# SENSORS.net
KiCad netlist of a schematic drawn in Altium Designer
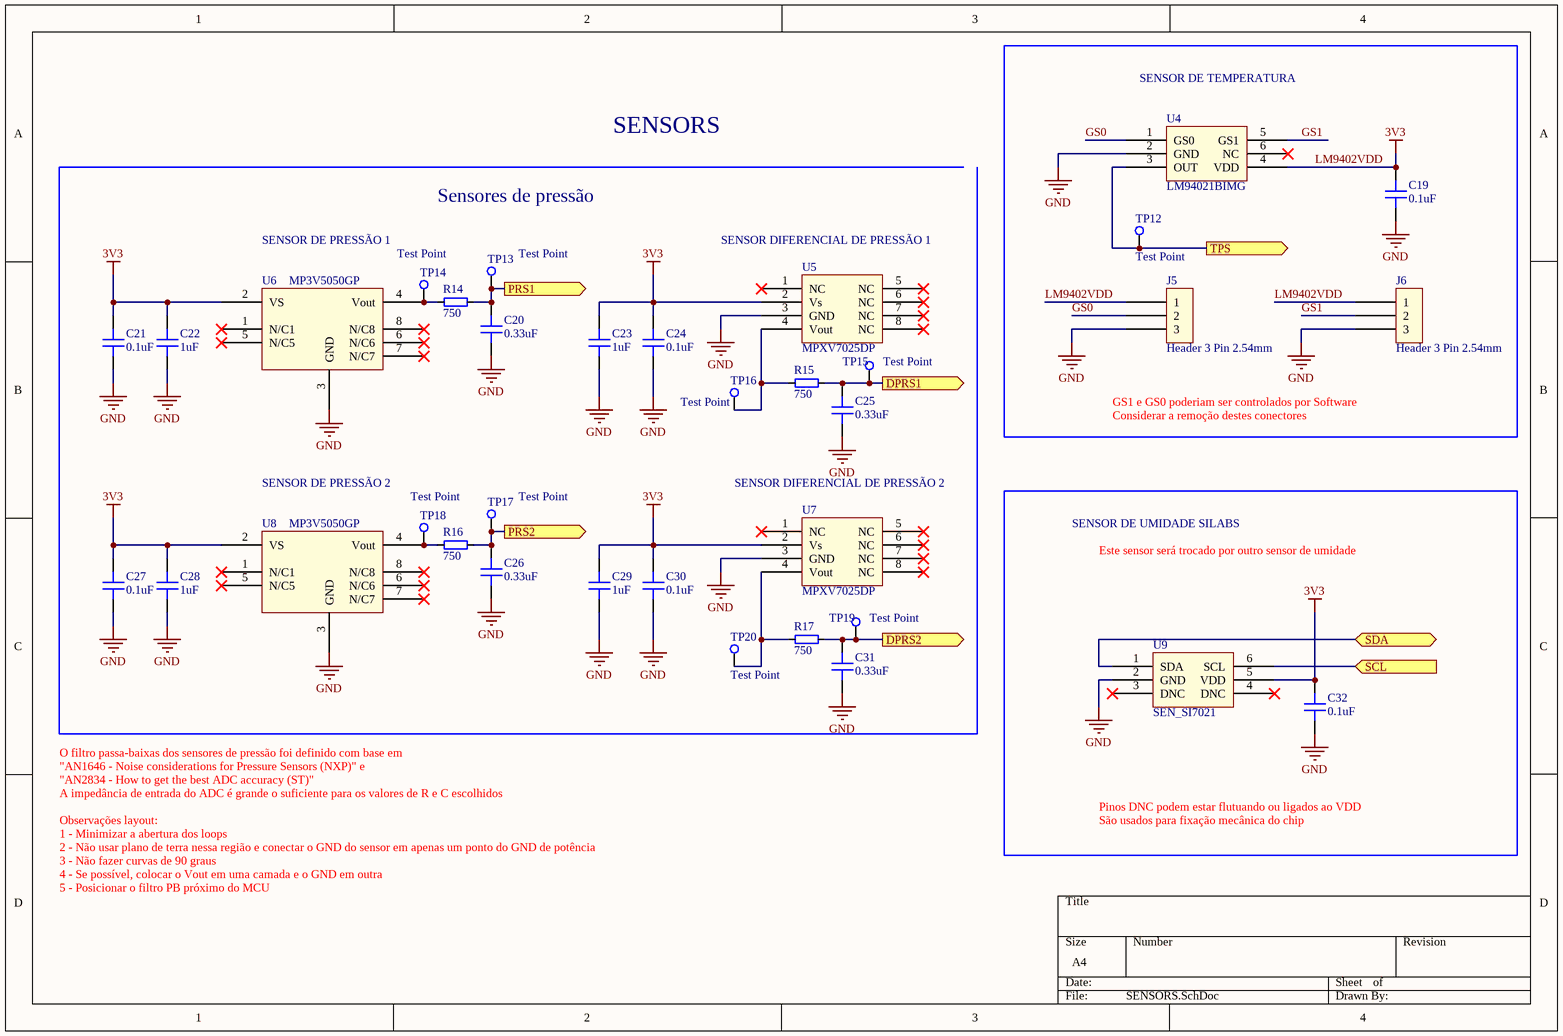
[diagram p0: SENSORS.SchDoc]

(export (version "E")
  (design (tool "Eeschema 10.0.6"))
  (components
    (comp (ref "C19")
      (value "0.1uF")
      (footprint "C_0805")
      (description "SMD/SMT 50V 0.1uF X7R 0805 10% Ceramic")
      (fields (field (name "VOLTAGE") "50V") (field (name "MANUFACTURER") "KEMET"))
      (libsource (lib "RespiradorLib") (part "C_0805_C0805C104K5RAC7411"))
    )
    (comp (ref "C20")
      (value "0.33uF")
      (footprint "C_0805")
      (description "SMD/SMT 50V 0.33uF X7R 0805 10%")
      (fields (field (name "VOLTAGE") "50V") (field (name "MANUFACTURER") "KEMET"))
      (libsource (lib "RespiradorLib") (part "C_0805_C0805C334K5RECTU"))
    )
    (comp (ref "C21")
      (value "0.1uF")
      (footprint "C_0805")
      (description "SMD/SMT 50V 0.1uF X7R 0805 10% Ceramic")
      (fields (field (name "VOLTAGE") "50V") (field (name "MANUFACTURER") "KEMET"))
      (libsource (lib "RespiradorLib") (part "C_0805_C0805C104K5RAC7411"))
    )
    (comp (ref "C22")
      (value "1uF")
      (footprint "C_0805")
      (description "SMD/SMT 0805 50V 1uF 10% AEC-Q200 Ceramic")
      (fields (field (name "VOLTAGE") "50V") (field (name "MANUFACTURER") "Taiyo Yuden"))
      (libsource (lib "RespiradorLib") (part "C_0805_UMF212B7105KGHT"))
    )
    (comp (ref "C23")
      (value "1uF")
      (footprint "C_0805")
      (description "SMD/SMT 0805 50V 1uF 10% AEC-Q200 Ceramic")
      (fields (field (name "VOLTAGE") "50V") (field (name "MANUFACTURER") "Taiyo Yuden"))
      (libsource (lib "RespiradorLib") (part "C_0805_UMF212B7105KGHT"))
    )
    (comp (ref "C24")
      (value "0.1uF")
      (footprint "C_0805")
      (description "SMD/SMT 50V 0.1uF X7R 0805 10% Ceramic")
      (fields (field (name "VOLTAGE") "50V") (field (name "MANUFACTURER") "KEMET"))
      (libsource (lib "RespiradorLib") (part "C_0805_C0805C104K5RAC7411"))
    )
    (comp (ref "C25")
      (value "0.33uF")
      (footprint "C_0805")
      (description "SMD/SMT 50V 0.33uF X7R 0805 10%")
      (fields (field (name "VOLTAGE") "50V") (field (name "MANUFACTURER") "KEMET"))
      (libsource (lib "RespiradorLib") (part "C_0805_C0805C334K5RECTU"))
    )
    (comp (ref "C26")
      (value "0.33uF")
      (footprint "C_0805")
      (description "SMD/SMT 50V 0.33uF X7R 0805 10%")
      (fields (field (name "VOLTAGE") "50V") (field (name "MANUFACTURER") "KEMET"))
      (libsource (lib "RespiradorLib") (part "C_0805_C0805C334K5RECTU"))
    )
    (comp (ref "C27")
      (value "0.1uF")
      (footprint "C_0805")
      (description "SMD/SMT 50V 0.1uF X7R 0805 10% Ceramic")
      (fields (field (name "VOLTAGE") "50V") (field (name "MANUFACTURER") "KEMET"))
      (libsource (lib "RespiradorLib") (part "C_0805_C0805C104K5RAC7411"))
    )
    (comp (ref "C28")
      (value "1uF")
      (footprint "C_0805")
      (description "SMD/SMT 0805 50V 1uF 10% AEC-Q200 Ceramic")
      (fields (field (name "VOLTAGE") "50V") (field (name "MANUFACTURER") "Taiyo Yuden"))
      (libsource (lib "RespiradorLib") (part "C_0805_UMF212B7105KGHT"))
    )
    (comp (ref "C29")
      (value "1uF")
      (footprint "C_0805")
      (description "SMD/SMT 0805 50V 1uF 10% AEC-Q200 Ceramic")
      (fields (field (name "VOLTAGE") "50V") (field (name "MANUFACTURER") "Taiyo Yuden"))
      (libsource (lib "RespiradorLib") (part "C_0805_UMF212B7105KGHT"))
    )
    (comp (ref "C30")
      (value "0.1uF")
      (footprint "C_0805")
      (description "SMD/SMT 50V 0.1uF X7R 0805 10% Ceramic")
      (fields (field (name "VOLTAGE") "50V") (field (name "MANUFACTURER") "KEMET"))
      (libsource (lib "RespiradorLib") (part "C_0805_C0805C104K5RAC7411"))
    )
    (comp (ref "C31")
      (value "0.33uF")
      (footprint "C_0805")
      (description "SMD/SMT 50V 0.33uF X7R 0805 10%")
      (fields (field (name "VOLTAGE") "50V") (field (name "MANUFACTURER") "KEMET"))
      (libsource (lib "RespiradorLib") (part "C_0805_C0805C334K5RECTU"))
    )
    (comp (ref "C32")
      (value "0.1uF")
      (footprint "C_0805")
      (description "SMD/SMT 50V 0.1uF X7R 0805 10% Ceramic")
      (fields (field (name "VOLTAGE") "50V") (field (name "MANUFACTURER") "KEMET"))
      (libsource (lib "RespiradorLib") (part "C_0805_C0805C104K5RAC7411"))
    )
    (comp (ref "J5")
      (value "Header 3 Pin 2.54mm")
      (footprint "Header 3 Pin 2.54mm")
      (libsource (lib "RespiradorLib") (part "Header 3 Pin 2.54mm"))
    )
    (comp (ref "J6")
      (value "Header 3 Pin 2.54mm")
      (footprint "Header 3 Pin 2.54mm")
      (libsource (lib "RespiradorLib") (part "Header 3 Pin 2.54mm"))
    )
    (comp (ref "R14")
      (value "750")
      (footprint "R_0805")
      (description "SMD 0805 750 OHM 5% AEC-Q200")
      (fields (field (name "MANUFACTURER") "Panasonic") (field (name "VOLTAGE") "150V"))
      (libsource (lib "RespiradorLib") (part "R_0805_ERJ-ERJ-6GEYJ751V"))
    )
    (comp (ref "R15")
      (value "750")
      (footprint "R_0805")
      (description "SMD 0805 750 OHM 5% AEC-Q200")
      (fields (field (name "MANUFACTURER") "Panasonic") (field (name "VOLTAGE") "150V"))
      (libsource (lib "RespiradorLib") (part "R_0805_ERJ-ERJ-6GEYJ751V"))
    )
    (comp (ref "R16")
      (value "750")
      (footprint "R_0805")
      (description "SMD 0805 750 OHM 5% AEC-Q200")
      (fields (field (name "MANUFACTURER") "Panasonic") (field (name "VOLTAGE") "150V"))
      (libsource (lib "RespiradorLib") (part "R_0805_ERJ-ERJ-6GEYJ751V"))
    )
    (comp (ref "R17")
      (value "750")
      (footprint "R_0805")
      (description "SMD 0805 750 OHM 5% AEC-Q200")
      (fields (field (name "MANUFACTURER") "Panasonic") (field (name "VOLTAGE") "150V"))
      (libsource (lib "RespiradorLib") (part "R_0805_ERJ-ERJ-6GEYJ751V"))
    )
    (comp (ref "TP12")
      (value "Test Point")
      (footprint "Test_Point")
      (libsource (lib "RespiradorLib") (part "Test Point"))
    )
    (comp (ref "TP13")
      (value "Test Point")
      (footprint "Test_Point")
      (libsource (lib "RespiradorLib") (part "Test Point"))
    )
    (comp (ref "TP14")
      (value "Test Point")
      (footprint "Test_Point")
      (libsource (lib "RespiradorLib") (part "Test Point"))
    )
    (comp (ref "TP15")
      (value "Test Point")
      (footprint "Test_Point")
      (libsource (lib "RespiradorLib") (part "Test Point"))
    )
    (comp (ref "TP16")
      (value "Test Point")
      (footprint "Test_Point")
      (libsource (lib "RespiradorLib") (part "Test Point"))
    )
    (comp (ref "TP17")
      (value "Test Point")
      (footprint "Test_Point")
      (libsource (lib "RespiradorLib") (part "Test Point"))
    )
    (comp (ref "TP18")
      (value "Test Point")
      (footprint "Test_Point")
      (libsource (lib "RespiradorLib") (part "Test Point"))
    )
    (comp (ref "TP19")
      (value "Test Point")
      (footprint "Test_Point")
      (libsource (lib "RespiradorLib") (part "Test Point"))
    )
    (comp (ref "TP20")
      (value "Test Point")
      (footprint "Test_Point")
      (libsource (lib "RespiradorLib") (part "Test Point"))
    )
    (comp (ref "U4")
      (value "LM94021BIMG")
      (footprint "LM94021BIMG")
      (description "IC TEMP SENSOR MULTI-GAIN SC70-5")
      (libsource (lib "RespiradorLib") (part "SEN_LM94021BIMG"))
    )
    (comp (ref "U5")
      (value "MPXV7025DP")
      (footprint "MPXV7025DP")
      (description "-25 to 25 kPa Differential Pressure Sensor DUAL PORT 8-SOP")
      (libsource (lib "RespiradorLib") (part "SEN_MPXV7025DP"))
    )
    (comp (ref "U6")
      (value "MP3V5050GP")
      (footprint "MP3V5050GP")
      (description "IC PRESSURE SENSOR 8-SOP 7PSI")
      (libsource (lib "RespiradorLib") (part "SEN_MP3V5050GP"))
    )
    (comp (ref "U7")
      (value "MPXV7025DP")
      (footprint "MPXV7025DP")
      (description "-25 to 25 kPa Differential Pressure Sensor DUAL PORT 8-SOP")
      (libsource (lib "RespiradorLib") (part "SEN_MPXV7025DP"))
    )
    (comp (ref "U8")
      (value "MP3V5050GP")
      (footprint "MP3V5050GP")
      (description "IC PRESSURE SENSOR 8-SOP 7PSI")
      (libsource (lib "RespiradorLib") (part "SEN_MP3V5050GP"))
    )
    (comp (ref "U9")
      (value "SEN_SI7021")
      (footprint "SI7021_6DFN")
      (description "Humidity Sensors Digital RH ( 3% max) & temperature sensor, commercial grade with cover/filter")
      (libsource (lib "RespiradorLib") (part "SEN_SI7021"))
    )
  )
  (nets
    (net (code "1") (name "/DPRS1") (class "Default")
      (node (ref "C25") (pin "2") (pinfunction "2_2") (pintype "passive"))
      (node (ref "R15") (pin "2") (pinfunction "2_2") (pintype "passive"))
      (node (ref "TP15") (pin "1") (pinfunction "TP_1") (pintype "passive"))
    )
    (net (code "2") (name "/DPRS2") (class "Default")
      (node (ref "C31") (pin "2") (pinfunction "2_2") (pintype "passive"))
      (node (ref "R17") (pin "2") (pinfunction "2_2") (pintype "passive"))
      (node (ref "TP19") (pin "1") (pinfunction "TP_1") (pintype "passive"))
    )
    (net (code "3") (name "/GS0") (class "Default")
      (node (ref "J5") (pin "2") (pinfunction "2_2") (pintype "passive"))
      (node (ref "U4") (pin "1") (pinfunction "GS0_1") (pintype "passive"))
    )
    (net (code "4") (name "/GS1") (class "Default")
      (node (ref "J6") (pin "2") (pinfunction "2_2") (pintype "passive"))
      (node (ref "U4") (pin "5") (pinfunction "GS1_5") (pintype "passive"))
    )
    (net (code "5") (name "/PRS1") (class "Default")
      (node (ref "C20") (pin "2") (pinfunction "2_2") (pintype "passive"))
      (node (ref "R14") (pin "2") (pinfunction "2_2") (pintype "passive"))
      (node (ref "TP13") (pin "1") (pinfunction "TP_1") (pintype "passive"))
    )
    (net (code "6") (name "/PRS2") (class "Default")
      (node (ref "C26") (pin "2") (pinfunction "2_2") (pintype "passive"))
      (node (ref "R16") (pin "2") (pinfunction "2_2") (pintype "passive"))
      (node (ref "TP17") (pin "1") (pinfunction "TP_1") (pintype "passive"))
    )
    (net (code "7") (name "/SCL") (class "Default")
      (node (ref "U9") (pin "6") (pinfunction "SCL_6") (pintype "passive"))
    )
    (net (code "8") (name "/SDA") (class "Default")
      (node (ref "U9") (pin "1") (pinfunction "SDA_1") (pintype "passive"))
    )
    (net (code "9") (name "/TPS") (class "Default")
      (node (ref "TP12") (pin "1") (pinfunction "TP_1") (pintype "passive"))
      (node (ref "U4") (pin "3") (pinfunction "OUT_3") (pintype "passive"))
    )
    (net (code "10") (name "3V3") (class "Default")
      (node (ref "C19") (pin "2") (pinfunction "2_2") (pintype "passive"))
      (node (ref "C21") (pin "2") (pinfunction "2_2") (pintype "passive"))
      (node (ref "C22") (pin "2") (pinfunction "2_2") (pintype "passive"))
      (node (ref "C23") (pin "2") (pinfunction "2_2") (pintype "passive"))
      (node (ref "C24") (pin "2") (pinfunction "2_2") (pintype "passive"))
      (node (ref "C27") (pin "2") (pinfunction "2_2") (pintype "passive"))
      (node (ref "C28") (pin "2") (pinfunction "2_2") (pintype "passive"))
      (node (ref "C29") (pin "2") (pinfunction "2_2") (pintype "passive"))
      (node (ref "C30") (pin "2") (pinfunction "2_2") (pintype "passive"))
      (node (ref "C32") (pin "2") (pinfunction "2_2") (pintype "passive"))
      (node (ref "J5") (pin "1") (pinfunction "1_1") (pintype "passive"))
      (node (ref "J6") (pin "1") (pinfunction "1_1") (pintype "passive"))
      (node (ref "U4") (pin "4") (pinfunction "VDD_4") (pintype "passive"))
      (node (ref "U5") (pin "2") (pinfunction "Vs_2") (pintype "passive"))
      (node (ref "U6") (pin "2") (pinfunction "VS_2") (pintype "passive"))
      (node (ref "U7") (pin "2") (pinfunction "Vs_2") (pintype "passive"))
      (node (ref "U8") (pin "2") (pinfunction "VS_2") (pintype "passive"))
      (node (ref "U9") (pin "5") (pinfunction "VDD_5") (pintype "passive"))
    )
    (net (code "11") (name "GND") (class "Default")
      (node (ref "C19") (pin "1") (pinfunction "1_1") (pintype "passive"))
      (node (ref "C20") (pin "1") (pinfunction "1_1") (pintype "passive"))
      (node (ref "C21") (pin "1") (pinfunction "1_1") (pintype "passive"))
      (node (ref "C22") (pin "1") (pinfunction "1_1") (pintype "passive"))
      (node (ref "C23") (pin "1") (pinfunction "1_1") (pintype "passive"))
      (node (ref "C24") (pin "1") (pinfunction "1_1") (pintype "passive"))
      (node (ref "C25") (pin "1") (pinfunction "1_1") (pintype "passive"))
      (node (ref "C26") (pin "1") (pinfunction "1_1") (pintype "passive"))
      (node (ref "C27") (pin "1") (pinfunction "1_1") (pintype "passive"))
      (node (ref "C28") (pin "1") (pinfunction "1_1") (pintype "passive"))
      (node (ref "C29") (pin "1") (pinfunction "1_1") (pintype "passive"))
      (node (ref "C30") (pin "1") (pinfunction "1_1") (pintype "passive"))
      (node (ref "C31") (pin "1") (pinfunction "1_1") (pintype "passive"))
      (node (ref "C32") (pin "1") (pinfunction "1_1") (pintype "passive"))
      (node (ref "J5") (pin "3") (pinfunction "3_3") (pintype "passive"))
      (node (ref "J6") (pin "3") (pinfunction "3_3") (pintype "passive"))
      (node (ref "U4") (pin "2") (pinfunction "GND_2") (pintype "passive"))
      (node (ref "U5") (pin "3") (pinfunction "GND_3") (pintype "passive"))
      (node (ref "U6") (pin "3") (pinfunction "GND_3") (pintype "passive"))
      (node (ref "U7") (pin "3") (pinfunction "GND_3") (pintype "passive"))
      (node (ref "U8") (pin "3") (pinfunction "GND_3") (pintype "passive"))
      (node (ref "U9") (pin "2") (pinfunction "GND_2") (pintype "passive"))
    )
    (net (code "12") (name "Net-(TP14-TP)") (class "Default")
      (node (ref "R14") (pin "1") (pinfunction "1_1") (pintype "passive"))
      (node (ref "TP14") (pin "1") (pinfunction "TP_1") (pintype "passive"))
      (node (ref "U6") (pin "4") (pinfunction "Vout_4") (pintype "passive"))
    )
    (net (code "13") (name "Net-(TP16-TP)") (class "Default")
      (node (ref "R15") (pin "1") (pinfunction "1_1") (pintype "passive"))
      (node (ref "TP16") (pin "1") (pinfunction "TP_1") (pintype "passive"))
      (node (ref "U5") (pin "4") (pinfunction "Vout_4") (pintype "passive"))
    )
    (net (code "14") (name "Net-(TP18-TP)") (class "Default")
      (node (ref "R16") (pin "1") (pinfunction "1_1") (pintype "passive"))
      (node (ref "TP18") (pin "1") (pinfunction "TP_1") (pintype "passive"))
      (node (ref "U8") (pin "4") (pinfunction "Vout_4") (pintype "passive"))
    )
    (net (code "15") (name "Net-(TP20-TP)") (class "Default")
      (node (ref "R17") (pin "1") (pinfunction "1_1") (pintype "passive"))
      (node (ref "TP20") (pin "1") (pinfunction "TP_1") (pintype "passive"))
      (node (ref "U7") (pin "4") (pinfunction "Vout_4") (pintype "passive"))
    )
    (net (code "16") (name "unconnected-(U4-NC-Pad6)") (class "Default")
      (node (ref "U4") (pin "6") (pinfunction "NC_6") (pintype "passive+no_connect"))
    )
    (net (code "17") (name "unconnected-(U5-NC-Pad1)") (class "Default")
      (node (ref "U5") (pin "1") (pinfunction "NC_1") (pintype "passive+no_connect"))
    )
    (net (code "18") (name "unconnected-(U5-NC-Pad5)") (class "Default")
      (node (ref "U5") (pin "5") (pinfunction "NC_5") (pintype "passive+no_connect"))
    )
    (net (code "19") (name "unconnected-(U5-NC-Pad6)") (class "Default")
      (node (ref "U5") (pin "6") (pinfunction "NC_6") (pintype "passive+no_connect"))
    )
    (net (code "20") (name "unconnected-(U5-NC-Pad7)") (class "Default")
      (node (ref "U5") (pin "7") (pinfunction "NC_7") (pintype "passive+no_connect"))
    )
    (net (code "21") (name "unconnected-(U5-NC-Pad8)") (class "Default")
      (node (ref "U5") (pin "8") (pinfunction "NC_8") (pintype "passive+no_connect"))
    )
    (net (code "22") (name "unconnected-(U6-N{slash}C1-Pad1)") (class "Default")
      (node (ref "U6") (pin "1") (pinfunction "N/C1_1") (pintype "passive+no_connect"))
    )
    (net (code "23") (name "unconnected-(U6-N{slash}C5-Pad5)") (class "Default")
      (node (ref "U6") (pin "5") (pinfunction "N/C5_5") (pintype "passive+no_connect"))
    )
    (net (code "24") (name "unconnected-(U6-N{slash}C6-Pad6)") (class "Default")
      (node (ref "U6") (pin "6") (pinfunction "N/C6_6") (pintype "passive+no_connect"))
    )
    (net (code "25") (name "unconnected-(U6-N{slash}C7-Pad7)") (class "Default")
      (node (ref "U6") (pin "7") (pinfunction "N/C7_7") (pintype "passive+no_connect"))
    )
    (net (code "26") (name "unconnected-(U6-N{slash}C8-Pad8)") (class "Default")
      (node (ref "U6") (pin "8") (pinfunction "N/C8_8") (pintype "passive+no_connect"))
    )
    (net (code "27") (name "unconnected-(U7-NC-Pad1)") (class "Default")
      (node (ref "U7") (pin "1") (pinfunction "NC_1") (pintype "passive+no_connect"))
    )
    (net (code "28") (name "unconnected-(U7-NC-Pad5)") (class "Default")
      (node (ref "U7") (pin "5") (pinfunction "NC_5") (pintype "passive+no_connect"))
    )
    (net (code "29") (name "unconnected-(U7-NC-Pad6)") (class "Default")
      (node (ref "U7") (pin "6") (pinfunction "NC_6") (pintype "passive+no_connect"))
    )
    (net (code "30") (name "unconnected-(U7-NC-Pad7)") (class "Default")
      (node (ref "U7") (pin "7") (pinfunction "NC_7") (pintype "passive+no_connect"))
    )
    (net (code "31") (name "unconnected-(U7-NC-Pad8)") (class "Default")
      (node (ref "U7") (pin "8") (pinfunction "NC_8") (pintype "passive+no_connect"))
    )
    (net (code "32") (name "unconnected-(U8-N{slash}C1-Pad1)") (class "Default")
      (node (ref "U8") (pin "1") (pinfunction "N/C1_1") (pintype "passive+no_connect"))
    )
    (net (code "33") (name "unconnected-(U8-N{slash}C5-Pad5)") (class "Default")
      (node (ref "U8") (pin "5") (pinfunction "N/C5_5") (pintype "passive+no_connect"))
    )
    (net (code "34") (name "unconnected-(U8-N{slash}C6-Pad6)") (class "Default")
      (node (ref "U8") (pin "6") (pinfunction "N/C6_6") (pintype "passive+no_connect"))
    )
    (net (code "35") (name "unconnected-(U8-N{slash}C7-Pad7)") (class "Default")
      (node (ref "U8") (pin "7") (pinfunction "N/C7_7") (pintype "passive+no_connect"))
    )
    (net (code "36") (name "unconnected-(U8-N{slash}C8-Pad8)") (class "Default")
      (node (ref "U8") (pin "8") (pinfunction "N/C8_8") (pintype "passive+no_connect"))
    )
    (net (code "37") (name "unconnected-(U9-DNC-Pad3)") (class "Default")
      (node (ref "U9") (pin "3") (pinfunction "DNC_3") (pintype "passive+no_connect"))
    )
    (net (code "38") (name "unconnected-(U9-DNC-Pad4)") (class "Default")
      (node (ref "U9") (pin "4") (pinfunction "DNC_4") (pintype "passive+no_connect"))
    )
  )
)
